# Sensors.net
KiCad netlist of a schematic drawn in Altium Designer
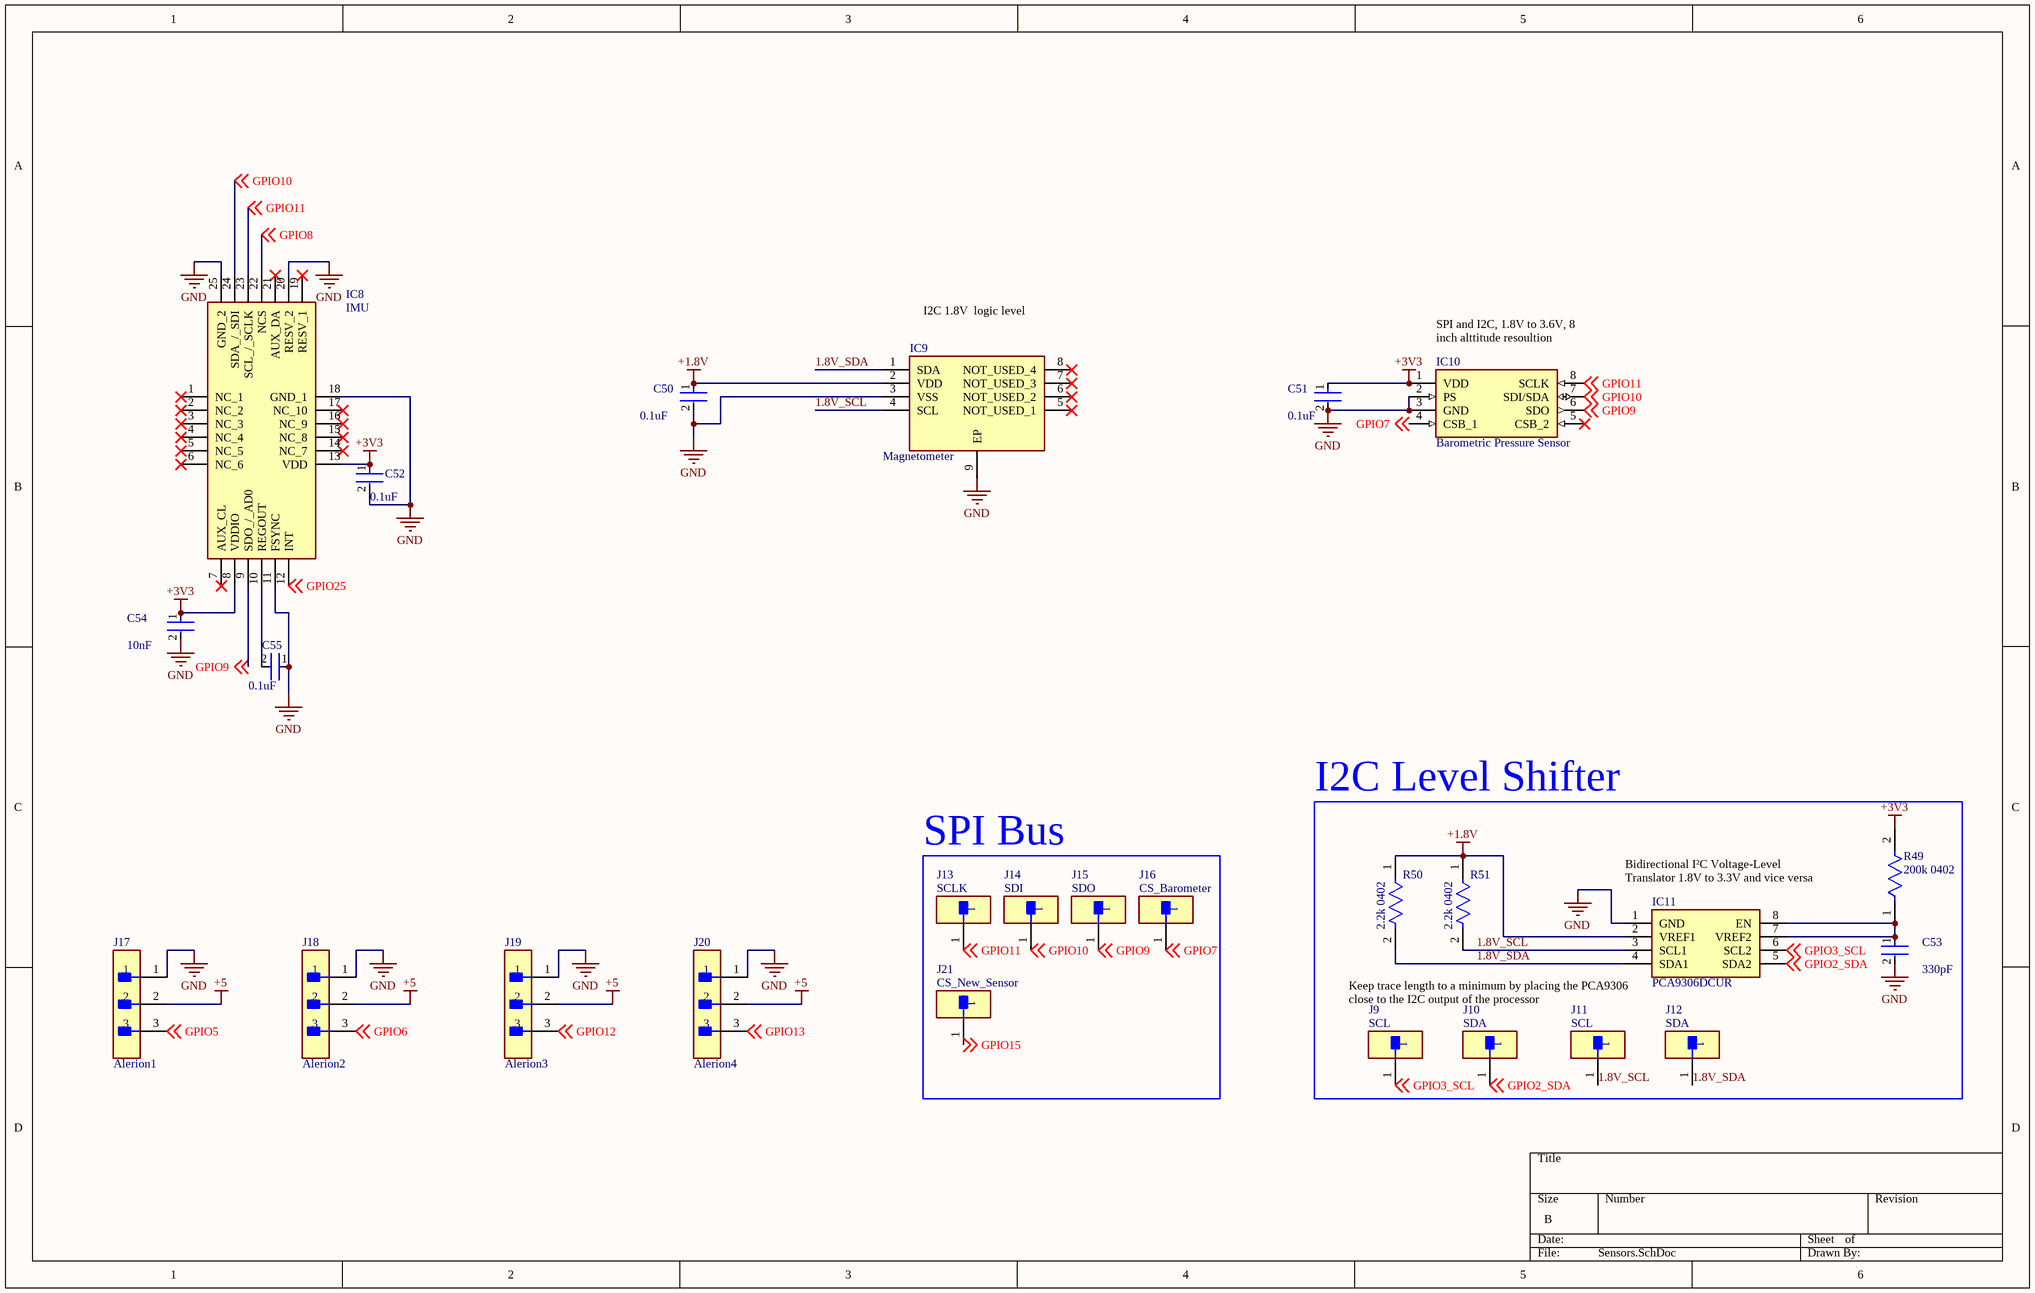
[diagram p0: Sensors.SchDoc]

(export (version "E")
  (design (tool "Eeschema 10.0.6"))
  (components
    (comp (ref "C50")
      (value "0.1uF")
      (footprint "FP-C0402-BB-MFG")
      (description "C307331")
      (fields
        (field (name "TOLERANCE") "0.2")
        (field (name "OCTOPART") "https://octopart.com/c0402c104m3pac7867-kemet-84304880")
      )
      (libsource (lib "Altium Content Vault") (part "b4654b650e69147ec39a6b967a45e02"))
    )
    (comp (ref "C51")
      (value "0.1uF")
      (footprint "FP-C0402-BB-MFG")
      (description "C307331")
      (fields
        (field (name "TOLERANCE") "0.2")
        (field (name "OCTOPART") "https://octopart.com/c0402c104m3pac7867-kemet-84304880")
      )
      (libsource (lib "Altium Content Vault") (part "b4654b650e69147ec39a6b967a45e02"))
    )
    (comp (ref "C52")
      (value "0.1uF")
      (footprint "FP-C0402-BB-MFG")
      (description "C307331")
      (fields
        (field (name "TOLERANCE") "0.2")
        (field (name "OCTOPART") "https://octopart.com/c0402c104m3pac7867-kemet-84304880")
      )
      (libsource (lib "Altium Content Vault") (part "b4654b650e69147ec39a6b967a45e02"))
    )
    (comp (ref "C53")
      (value "330pF")
      (footprint "FP-C0402-BB-MFG")
      (description "C13533")
      (fields
        (field (name "TOLERANCE") "0.2")
        (field (name "OCTOPART") "https://octopart.com/c0402c104m3pac7867-kemet-84304880")
      )
      (libsource (lib "Altium Content Vault") (part "b4654b650e69147ec39a6b967a45e02"))
    )
    (comp (ref "C54")
      (value "10nF")
      (footprint "FP-C0402-BB-MFG")
      (description "C15195")
      (fields
        (field (name "TOLERANCE") "0.2")
        (field (name "OCTOPART") "https://octopart.com/c0402c104m3pac7867-kemet-84304880")
      )
      (libsource (lib "Altium Content Vault") (part "b4654b650e69147ec39a6b967a45e02"))
    )
    (comp (ref "C55")
      (value "0.1uF")
      (footprint "FP-C0402-BB-MFG")
      (description "C307331")
      (fields
        (field (name "TOLERANCE") "0.2")
        (field (name "OCTOPART") "https://octopart.com/c0402c104m3pac7867-kemet-84304880")
      )
      (libsource (lib "Altium Content Vault") (part "b4654b650e69147ec39a6b967a45e02"))
    )
    (comp (ref "IC8")
      (value "IMU")
      (footprint "SamacSys:QFN40P300X300X95-25N-D")
      (description "C50278")
      (fields
        (field (name "MANUFACTURER_PART_NUMBER") "MPU-6500")
        (field (name "MOUSER PART NUMBER") "410-MPU-6500")
      )
      (libsource (lib "*") (part "MPU-6500"))
    )
    (comp (ref "IC9")
      (value "Magnetometer")
      (footprint "SamacSys:SON40P250X200X40-9N-D")
      (description "C17495733\r\nDigikey Replacment Part Just in Case: MLX90392ELQ-AAA-010-RE (10X finer resolution)")
      (fields
        (field (name "MANUFACTURER_PART_NUMBER") "MLX90392ELQ-AAA-011-RE")
        (field (name "MOUSER PART NUMBER") "482-90392ELQAAA011RE")
      )
      (libsource (lib "*") (part "MLX90392ELQ-AAA-011-RE"))
    )
    (comp (ref "IC10")
      (value "Barometric Pressure Sensor")
      (footprint "SamacSys:MS5607-02BA03")
      (description "C97627")
      (fields
        (field (name "MANUFACTURER_PART_NUMBER") "MS560702BA03-50")
        (field (name "MOUSER PART NUMBER") "824-MS560702BA03-50")
      )
      (libsource (lib "*") (part "MS560702BA03-50"))
    )
    (comp (ref "IC11")
      (value "PCA9306DCUR")
      (footprint "SamacSys:SOP50P310X90-8N")
      (description "C33196")
      (fields (field (name "MOUSER PART NUMBER") "595-PCA9306DCUR"))
      (libsource (lib "*") (part "PCA9306DCUR"))
    )
    (comp (ref "J9")
      (value "SCL")
      (footprint "FP-5015-MFG")
      (description "PC TEST POINT MINIATURE")
      (fields (field (name "MANUFACTURER PART NUMBER") "5015") (field (name "MANUFACTURER") "keystone"))
      (libsource (lib "Altium Content Vault") (part "dd45045ce8184df9e99e12baf3f412c"))
    )
    (comp (ref "J10")
      (value "SDA")
      (footprint "FP-5015-MFG")
      (description "PC TEST POINT MINIATURE")
      (fields (field (name "MANUFACTURER PART NUMBER") "5015") (field (name "MANUFACTURER") "keystone"))
      (libsource (lib "Altium Content Vault") (part "dd45045ce8184df9e99e12baf3f412c"))
    )
    (comp (ref "J11")
      (value "SCL")
      (footprint "FP-5015-MFG")
      (description "PC TEST POINT MINIATURE")
      (fields (field (name "MANUFACTURER PART NUMBER") "5015") (field (name "MANUFACTURER") "keystone"))
      (libsource (lib "Altium Content Vault") (part "dd45045ce8184df9e99e12baf3f412c"))
    )
    (comp (ref "J12")
      (value "SDA")
      (footprint "FP-5015-MFG")
      (description "PC TEST POINT MINIATURE")
      (fields (field (name "MANUFACTURER PART NUMBER") "5015") (field (name "MANUFACTURER") "keystone"))
      (libsource (lib "Altium Content Vault") (part "dd45045ce8184df9e99e12baf3f412c"))
    )
    (comp (ref "J13")
      (value "SCLK")
      (footprint "FP-5015-MFG")
      (description "PC TEST POINT MINIATURE")
      (fields (field (name "MANUFACTURER PART NUMBER") "5015") (field (name "MANUFACTURER") "keystone"))
      (libsource (lib "Altium Content Vault") (part "dd45045ce8184df9e99e12baf3f412c"))
    )
    (comp (ref "J14")
      (value "SDI")
      (footprint "FP-5015-MFG")
      (description "PC TEST POINT MINIATURE")
      (fields (field (name "MANUFACTURER PART NUMBER") "5015") (field (name "MANUFACTURER") "keystone"))
      (libsource (lib "Altium Content Vault") (part "dd45045ce8184df9e99e12baf3f412c"))
    )
    (comp (ref "J15")
      (value "SDO")
      (footprint "FP-5015-MFG")
      (description "PC TEST POINT MINIATURE")
      (fields (field (name "MANUFACTURER PART NUMBER") "5015") (field (name "MANUFACTURER") "keystone"))
      (libsource (lib "Altium Content Vault") (part "dd45045ce8184df9e99e12baf3f412c"))
    )
    (comp (ref "J16")
      (value "CS_Barometer")
      (footprint "FP-5015-MFG")
      (description "PC TEST POINT MINIATURE")
      (fields (field (name "MANUFACTURER PART NUMBER") "5015") (field (name "MANUFACTURER") "keystone"))
      (libsource (lib "Altium Content Vault") (part "dd45045ce8184df9e99e12baf3f412c"))
    )
    (comp (ref "J17")
      (value "Alerion1")
      (footprint "FP-TSW-103-14-G-S-MFG")
      (description "CONN HEADER VERT 3POS 2.54MM")
      (libsource (lib "Altium Content Vault") (part "cd3439d6ef35ae5d9b27ec4fdd3e828"))
    )
    (comp (ref "J18")
      (value "Alerion2")
      (footprint "FP-TSW-103-14-G-S-MFG")
      (description "CONN HEADER VERT 3POS 2.54MM")
      (libsource (lib "Altium Content Vault") (part "cd3439d6ef35ae5d9b27ec4fdd3e828"))
    )
    (comp (ref "J19")
      (value "Alerion3")
      (footprint "FP-TSW-103-14-G-S-MFG")
      (description "CONN HEADER VERT 3POS 2.54MM")
      (libsource (lib "Altium Content Vault") (part "cd3439d6ef35ae5d9b27ec4fdd3e828"))
    )
    (comp (ref "J20")
      (value "Alerion4")
      (footprint "FP-TSW-103-14-G-S-MFG")
      (description "CONN HEADER VERT 3POS 2.54MM")
      (libsource (lib "Altium Content Vault") (part "cd3439d6ef35ae5d9b27ec4fdd3e828"))
    )
    (comp (ref "J21")
      (value "CS_New_Sensor")
      (footprint "FP-5015-MFG")
      (description "PC TEST POINT MINIATURE")
      (fields (field (name "MANUFACTURER PART NUMBER") "5015") (field (name "MANUFACTURER") "keystone"))
      (libsource (lib "Altium Content Vault") (part "dd45045ce8184df9e99e12baf3f412c"))
    )
    (comp (ref "R49")
      (value "200k 0402")
      (footprint "FP-RMCF0402-MFG")
      (description "C25764")
      (fields (field (name "TOLERANCE") "5%"))
      (libsource (lib "Altium Content Vault") (part "1029c3af85768c4190bb7ad29bc67b5"))
    )
    (comp (ref "R50")
      (value "2.2k 0402")
      (footprint "FP-RMCF0402-MFG")
      (description "C25879")
      (fields (field (name "TOLERANCE") "5%"))
      (libsource (lib "Altium Content Vault") (part "1029c3af85768c4190bb7ad29bc67b5"))
    )
    (comp (ref "R51")
      (value "2.2k 0402")
      (footprint "FP-RMCF0402-MFG")
      (description "C25879")
      (fields (field (name "TOLERANCE") "5%"))
      (libsource (lib "Altium Content Vault") (part "1029c3af85768c4190bb7ad29bc67b5"))
    )
  )
  (nets
    (net (code "1") (name "+1.8V") (class "Default")
      (node (ref "C50") (pin "1") (pinfunction "1_1") (pintype "passive"))
      (node (ref "IC11") (pin "2") (pinfunction "VREF1_2") (pintype "passive"))
      (node (ref "IC9") (pin "2") (pinfunction "VDD_2") (pintype "passive"))
      (node (ref "R50") (pin "1") (pinfunction "1_1") (pintype "passive"))
      (node (ref "R51") (pin "1") (pinfunction "1_1") (pintype "passive"))
    )
    (net (code "2") (name "+3V3") (class "Default")
      (node (ref "C51") (pin "1") (pinfunction "1_1") (pintype "passive"))
      (node (ref "C52") (pin "1") (pinfunction "1_1") (pintype "passive"))
      (node (ref "C54") (pin "1") (pinfunction "1_1") (pintype "passive"))
      (node (ref "IC10") (pin "1") (pinfunction "VDD_1") (pintype "power_in"))
      (node (ref "IC8") (pin "13") (pinfunction "VDD_13") (pintype "passive"))
      (node (ref "IC8") (pin "8") (pinfunction "VDDIO_8") (pintype "passive"))
      (node (ref "R49") (pin "2") (pinfunction "2_2") (pintype "passive"))
    )
    (net (code "3") (name "+5") (class "Default")
      (node (ref "J17") (pin "2") (pinfunction "2_2") (pintype "passive"))
      (node (ref "J18") (pin "2") (pinfunction "2_2") (pintype "passive"))
      (node (ref "J19") (pin "2") (pinfunction "2_2") (pintype "passive"))
      (node (ref "J20") (pin "2") (pinfunction "2_2") (pintype "passive"))
    )
    (net (code "4") (name "/1.8V_SCL") (class "Default")
      (node (ref "IC11") (pin "3") (pinfunction "SCL1_3") (pintype "passive"))
      (node (ref "IC9") (pin "4") (pinfunction "SCL_4") (pintype "passive"))
      (node (ref "J11") (pin "1") (pinfunction "1_1") (pintype "passive"))
      (node (ref "R51") (pin "2") (pinfunction "2_2") (pintype "passive"))
    )
    (net (code "5") (name "/1.8V_SDA") (class "Default")
      (node (ref "IC11") (pin "4") (pinfunction "SDA1_4") (pintype "passive"))
      (node (ref "IC9") (pin "1") (pinfunction "SDA_1") (pintype "passive"))
      (node (ref "J12") (pin "1") (pinfunction "1_1") (pintype "passive"))
      (node (ref "R50") (pin "2") (pinfunction "2_2") (pintype "passive"))
    )
    (net (code "6") (name "GND") (class "Default")
      (node (ref "C50") (pin "2") (pinfunction "2_2") (pintype "passive"))
      (node (ref "C51") (pin "2") (pinfunction "2_2") (pintype "passive"))
      (node (ref "C52") (pin "2") (pinfunction "2_2") (pintype "passive"))
      (node (ref "C53") (pin "2") (pinfunction "2_2") (pintype "passive"))
      (node (ref "C54") (pin "2") (pinfunction "2_2") (pintype "passive"))
      (node (ref "C55") (pin "1") (pinfunction "1_1") (pintype "passive"))
      (node (ref "IC10") (pin "2") (pinfunction "PS_2") (pintype "input"))
      (node (ref "IC10") (pin "3") (pinfunction "GND_3") (pintype "power_in"))
      (node (ref "IC11") (pin "1") (pinfunction "GND_1") (pintype "passive"))
      (node (ref "IC8") (pin "11") (pinfunction "FSYNC_11") (pintype "passive"))
      (node (ref "IC8") (pin "18") (pinfunction "GND_1_18") (pintype "passive"))
      (node (ref "IC8") (pin "20") (pinfunction "RESV_2_20") (pintype "passive"))
      (node (ref "IC8") (pin "25") (pinfunction "GND_2_25") (pintype "passive"))
      (node (ref "IC9") (pin "3") (pinfunction "VSS_3") (pintype "passive"))
      (node (ref "IC9") (pin "9") (pinfunction "EP_9") (pintype "passive"))
      (node (ref "J17") (pin "1") (pinfunction "1_1") (pintype "passive"))
      (node (ref "J18") (pin "1") (pinfunction "1_1") (pintype "passive"))
      (node (ref "J19") (pin "1") (pinfunction "1_1") (pintype "passive"))
      (node (ref "J20") (pin "1") (pinfunction "1_1") (pintype "passive"))
    )
    (net (code "7") (name "GPIO2_SDA") (class "Default")
      (node (ref "IC11") (pin "5") (pinfunction "SDA2_5") (pintype "passive"))
      (node (ref "J10") (pin "1") (pinfunction "1_1") (pintype "passive"))
    )
    (net (code "8") (name "GPIO3_SCL") (class "Default")
      (node (ref "IC11") (pin "6") (pinfunction "SCL2_6") (pintype "passive"))
      (node (ref "J9") (pin "1") (pinfunction "1_1") (pintype "passive"))
    )
    (net (code "9") (name "GPIO5") (class "Default")
      (node (ref "J17") (pin "3") (pinfunction "3_3") (pintype "passive"))
    )
    (net (code "10") (name "GPIO6") (class "Default")
      (node (ref "J18") (pin "3") (pinfunction "3_3") (pintype "passive"))
    )
    (net (code "11") (name "GPIO7") (class "Default")
      (node (ref "IC10") (pin "4") (pinfunction "CSB_1_4") (pintype "input"))
      (node (ref "J16") (pin "1") (pinfunction "1_1") (pintype "passive"))
    )
    (net (code "12") (name "GPIO8") (class "Default")
      (node (ref "IC8") (pin "22") (pinfunction "NCS_22") (pintype "passive"))
    )
    (net (code "13") (name "GPIO9") (class "Default")
      (node (ref "IC10") (pin "6") (pinfunction "SDO_6") (pintype "output"))
      (node (ref "IC8") (pin "9") (pinfunction "SDO_/_AD0_9") (pintype "passive"))
      (node (ref "J15") (pin "1") (pinfunction "1_1") (pintype "passive"))
    )
    (net (code "14") (name "GPIO10") (class "Default")
      (node (ref "IC10") (pin "7") (pinfunction "SDI/SDA_7") (pintype "bidirectional"))
      (node (ref "IC8") (pin "24") (pinfunction "SDA_/_SDI_24") (pintype "passive"))
      (node (ref "J14") (pin "1") (pinfunction "1_1") (pintype "passive"))
    )
    (net (code "15") (name "GPIO11") (class "Default")
      (node (ref "IC10") (pin "8") (pinfunction "SCLK_8") (pintype "input"))
      (node (ref "IC8") (pin "23") (pinfunction "SCL_/_SCLK_23") (pintype "passive"))
      (node (ref "J13") (pin "1") (pinfunction "1_1") (pintype "passive"))
    )
    (net (code "16") (name "GPIO12") (class "Default")
      (node (ref "J19") (pin "3") (pinfunction "3_3") (pintype "passive"))
    )
    (net (code "17") (name "GPIO13") (class "Default")
      (node (ref "J20") (pin "3") (pinfunction "3_3") (pintype "passive"))
    )
    (net (code "18") (name "GPIO15") (class "Default")
      (node (ref "J21") (pin "1") (pinfunction "1_1") (pintype "passive"))
    )
    (net (code "19") (name "GPIO25") (class "Default")
      (node (ref "IC8") (pin "12") (pinfunction "INT_12") (pintype "passive"))
    )
    (net (code "20") (name "Net-(IC8-REGOUT)") (class "Default")
      (node (ref "C55") (pin "2") (pinfunction "2_2") (pintype "passive"))
      (node (ref "IC8") (pin "10") (pinfunction "REGOUT_10") (pintype "passive"))
    )
    (net (code "21") (name "Net-(IC11-EN)") (class "Default")
      (node (ref "C53") (pin "1") (pinfunction "1_1") (pintype "passive"))
      (node (ref "IC11") (pin "7") (pinfunction "VREF2_7") (pintype "passive"))
      (node (ref "IC11") (pin "8") (pinfunction "EN_8") (pintype "passive"))
      (node (ref "R49") (pin "1") (pinfunction "1_1") (pintype "passive"))
    )
    (net (code "22") (name "unconnected-(IC8-AUX_CL-Pad7)") (class "Default")
      (node (ref "IC8") (pin "7") (pinfunction "AUX_CL_7") (pintype "passive+no_connect"))
    )
    (net (code "23") (name "unconnected-(IC8-AUX_DA-Pad21)") (class "Default")
      (node (ref "IC8") (pin "21") (pinfunction "AUX_DA_21") (pintype "passive+no_connect"))
    )
    (net (code "24") (name "unconnected-(IC8-NC_1-Pad1)") (class "Default")
      (node (ref "IC8") (pin "1") (pinfunction "NC_1_1") (pintype "passive+no_connect"))
    )
    (net (code "25") (name "unconnected-(IC8-NC_2-Pad2)") (class "Default")
      (node (ref "IC8") (pin "2") (pinfunction "NC_2_2") (pintype "passive+no_connect"))
    )
    (net (code "26") (name "unconnected-(IC8-NC_3-Pad3)") (class "Default")
      (node (ref "IC8") (pin "3") (pinfunction "NC_3_3") (pintype "passive+no_connect"))
    )
    (net (code "27") (name "unconnected-(IC8-NC_4-Pad4)") (class "Default")
      (node (ref "IC8") (pin "4") (pinfunction "NC_4_4") (pintype "passive+no_connect"))
    )
    (net (code "28") (name "unconnected-(IC8-NC_5-Pad5)") (class "Default")
      (node (ref "IC8") (pin "5") (pinfunction "NC_5_5") (pintype "passive+no_connect"))
    )
    (net (code "29") (name "unconnected-(IC8-NC_6-Pad6)") (class "Default")
      (node (ref "IC8") (pin "6") (pinfunction "NC_6_6") (pintype "passive+no_connect"))
    )
    (net (code "30") (name "unconnected-(IC8-NC_7-Pad14)") (class "Default")
      (node (ref "IC8") (pin "14") (pinfunction "NC_7_14") (pintype "passive+no_connect"))
    )
    (net (code "31") (name "unconnected-(IC8-NC_8-Pad15)") (class "Default")
      (node (ref "IC8") (pin "15") (pinfunction "NC_8_15") (pintype "passive+no_connect"))
    )
    (net (code "32") (name "unconnected-(IC8-NC_9-Pad16)") (class "Default")
      (node (ref "IC8") (pin "16") (pinfunction "NC_9_16") (pintype "passive+no_connect"))
    )
    (net (code "33") (name "unconnected-(IC8-NC_10-Pad17)") (class "Default")
      (node (ref "IC8") (pin "17") (pinfunction "NC_10_17") (pintype "passive+no_connect"))
    )
    (net (code "34") (name "unconnected-(IC8-RESV_1-Pad19)") (class "Default")
      (node (ref "IC8") (pin "19") (pinfunction "RESV_1_19") (pintype "passive+no_connect"))
    )
    (net (code "35") (name "unconnected-(IC9-NOT_USED_1-Pad5)") (class "Default")
      (node (ref "IC9") (pin "5") (pinfunction "NOT_USED_1_5") (pintype "passive+no_connect"))
    )
    (net (code "36") (name "unconnected-(IC9-NOT_USED_2-Pad6)") (class "Default")
      (node (ref "IC9") (pin "6") (pinfunction "NOT_USED_2_6") (pintype "passive+no_connect"))
    )
    (net (code "37") (name "unconnected-(IC9-NOT_USED_3-Pad7)") (class "Default")
      (node (ref "IC9") (pin "7") (pinfunction "NOT_USED_3_7") (pintype "passive+no_connect"))
    )
    (net (code "38") (name "unconnected-(IC9-NOT_USED_4-Pad8)") (class "Default")
      (node (ref "IC9") (pin "8") (pinfunction "NOT_USED_4_8") (pintype "passive+no_connect"))
    )
    (net (code "39") (name "unconnected-(IC10-CSB_2-Pad5)") (class "Default")
      (node (ref "IC10") (pin "5") (pinfunction "CSB_2_5") (pintype "input+no_connect"))
    )
  )
)
